# Esquema.net
KiCad netlist of a schematic drawn in EAGLE
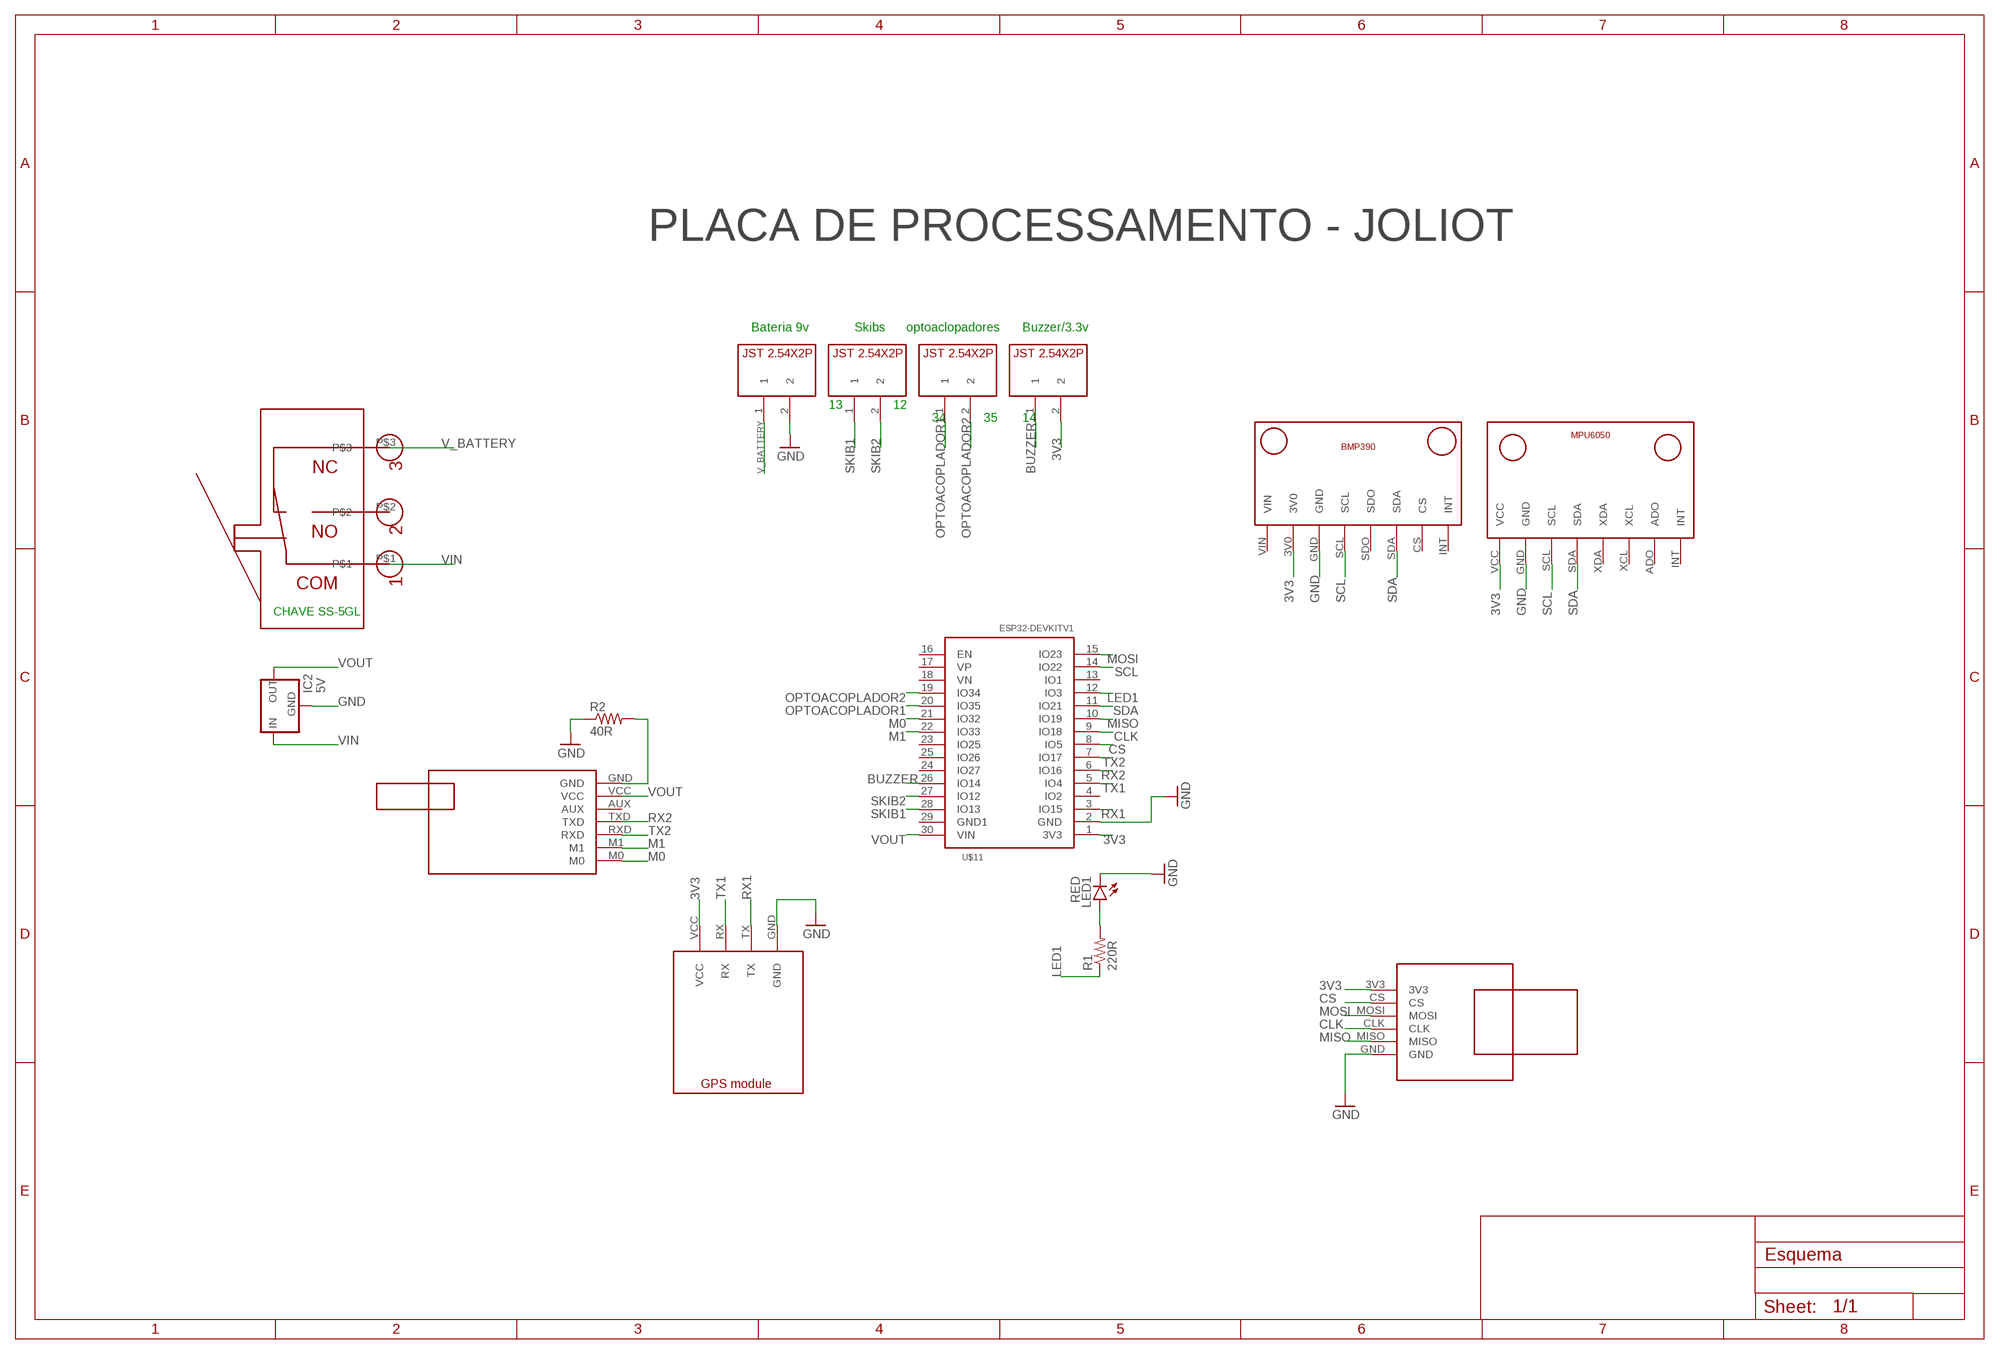
[diagram p0: schematic, sheet 1]

(export (version "E")
  (design (tool "Eeschema 10.0.6"))
  (components
    (comp (ref "IC2")
      (value "5V")
      (footprint "eagle-import:78XXL")
      (libsource (lib "eagle-import") (part "78XXL"))
    )
    (comp (ref "LED1")
      (value "RED")
      (footprint "eagle-import:LED5MM")
      (libsource (lib "eagle-import") (part "LED5MM"))
    )
    (comp (ref "R1")
      (value "220R")
      (footprint "eagle-import:0309_12")
      (libsource (lib "eagle-import") (part "R-US_0309/12"))
    )
    (comp (ref "R2")
      (value "40R")
      (footprint "eagle-import:0309_12")
      (libsource (lib "eagle-import") (part "R-US_0309/12"))
    )
    (comp (ref "U$1")
      (value "BMP390V1")
      (footprint "eagle-import:BMP390_FOOTPRINT")
      (libsource (lib "eagle-import") (part "BMP390V1"))
    )
    (comp (ref "U$2")
      (value "E22-400T30D")
      (footprint "eagle-import:E22-400T30D_FOOTPRINT")
      (libsource (lib "eagle-import") (part "E22-400T30D"))
    )
    (comp (ref "U$3")
      (value "GPS_MODULE")
      (footprint "eagle-import:GPS_MODULE_FOOTPRINT")
      (libsource (lib "eagle-import") (part "GPS_MODULE"))
    )
    (comp (ref "U$4")
      (value "JST2.54X2P")
      (footprint "eagle-import:JST2.54X2P_FOOTPRINT")
      (libsource (lib "eagle-import") (part "JST2.54X2P"))
    )
    (comp (ref "U$5")
      (value "JST2.54X2P")
      (footprint "eagle-import:JST2.54X2P_FOOTPRINT")
      (libsource (lib "eagle-import") (part "JST2.54X2P"))
    )
    (comp (ref "U$6")
      (value "JST2.54X2P")
      (footprint "eagle-import:JST2.54X2P_FOOTPRINT")
      (libsource (lib "eagle-import") (part "JST2.54X2P"))
    )
    (comp (ref "U$7")
      (value "JST2.54X2P")
      (footprint "eagle-import:JST2.54X2P_FOOTPRINT")
      (libsource (lib "eagle-import") (part "JST2.54X2P"))
    )
    (comp (ref "U$8")
      (value "MICROSD_SMALL_READER")
      (footprint "eagle-import:MICROSD_SMALL_READER_FOOTPRINT")
      (libsource (lib "eagle-import") (part "MICROSD_SMALL_READER"))
    )
    (comp (ref "U$9")
      (value "MPU6050V1")
      (footprint "eagle-import:MPU6050_FOOTPRINT")
      (libsource (lib "eagle-import") (part "MPU6050V1"))
    )
    (comp (ref "U$11")
      (value "ESP32DEVKITV1")
      (footprint "eagle-import:ESP32-DEVKITV1")
      (libsource (lib "eagle-import") (part "ESP32DEVKITV1"))
    )
    (comp (ref "U$12")
      (value "CHAVE_SS-5GL")
      (footprint "eagle-import:CHAVESS-5GL")
      (libsource (lib "eagle-import") (part "CHAVE_SS-5GL"))
    )
  )
  (nets
    (net (code "1") (name "/3V3") (class "Default")
      (node (ref "U$1") (pin "3V0") (pinfunction "3V0_3V0") (pintype "bidirectional"))
      (node (ref "U$11") (pin "1") (pinfunction "3V3_1") (pintype "bidirectional"))
      (node (ref "U$3") (pin "VCC") (pinfunction "VCC_VCC") (pintype "bidirectional"))
      (node (ref "U$4") (pin "2") (pinfunction "2_2") (pintype "bidirectional"))
      (node (ref "U$8") (pin "3V3") (pinfunction "3V3_3V3") (pintype "bidirectional"))
      (node (ref "U$9") (pin "VCC") (pinfunction "VCC_VCC") (pintype "bidirectional"))
    )
    (net (code "2") (name "/BUZZER") (class "Default")
      (node (ref "U$11") (pin "26") (pinfunction "IO14_26") (pintype "bidirectional"))
      (node (ref "U$4") (pin "1") (pinfunction "1_1") (pintype "bidirectional"))
    )
    (net (code "3") (name "/CLK") (class "Default")
      (node (ref "U$11") (pin "9") (pinfunction "IO18_9") (pintype "bidirectional"))
      (node (ref "U$8") (pin "CLK") (pinfunction "CLK_CLK") (pintype "bidirectional"))
    )
    (net (code "4") (name "/CS") (class "Default")
      (node (ref "U$11") (pin "8") (pinfunction "IO5_8") (pintype "bidirectional"))
      (node (ref "U$8") (pin "CS") (pinfunction "CS_CS") (pintype "bidirectional"))
    )
    (net (code "5") (name "/LED1") (class "Default")
      (node (ref "R1") (pin "1") (pinfunction "1_1") (pintype "passive"))
      (node (ref "U$11") (pin "12") (pinfunction "IO3_12") (pintype "bidirectional"))
    )
    (net (code "6") (name "/M0") (class "Default")
      (node (ref "U$11") (pin "21") (pinfunction "IO32_21") (pintype "bidirectional"))
      (node (ref "U$2") (pin "M0") (pinfunction "M0_M0") (pintype "bidirectional"))
    )
    (net (code "7") (name "/M1") (class "Default")
      (node (ref "U$11") (pin "22") (pinfunction "IO33_22") (pintype "bidirectional"))
      (node (ref "U$2") (pin "M1") (pinfunction "M1_M1") (pintype "bidirectional"))
    )
    (net (code "8") (name "/MISO") (class "Default")
      (node (ref "U$11") (pin "10") (pinfunction "IO19_10") (pintype "bidirectional"))
      (node (ref "U$8") (pin "MISO") (pinfunction "MISO_MISO") (pintype "bidirectional"))
    )
    (net (code "9") (name "/MOSI") (class "Default")
      (node (ref "U$11") (pin "15") (pinfunction "IO23_15") (pintype "bidirectional"))
      (node (ref "U$8") (pin "MOSI") (pinfunction "MOSI_MOSI") (pintype "bidirectional"))
    )
    (net (code "10") (name "/OPTOACOPLADOR1") (class "Default")
      (node (ref "U$11") (pin "20") (pinfunction "IO35_20") (pintype "bidirectional"))
      (node (ref "U$5") (pin "1") (pinfunction "1_1") (pintype "bidirectional"))
    )
    (net (code "11") (name "/OPTOACOPLADOR2") (class "Default")
      (node (ref "U$11") (pin "19") (pinfunction "IO34_19") (pintype "bidirectional"))
      (node (ref "U$5") (pin "2") (pinfunction "2_2") (pintype "bidirectional"))
    )
    (net (code "12") (name "/RX1") (class "Default")
      (node (ref "U$11") (pin "3") (pinfunction "IO15_3") (pintype "bidirectional"))
      (node (ref "U$3") (pin "TX") (pinfunction "TX_TX") (pintype "bidirectional"))
    )
    (net (code "13") (name "/RX2") (class "Default")
      (node (ref "U$11") (pin "6") (pinfunction "IO16_6") (pintype "bidirectional"))
      (node (ref "U$2") (pin "TXD") (pinfunction "TXD_TXD") (pintype "bidirectional"))
    )
    (net (code "14") (name "/SCL") (class "Default")
      (node (ref "U$1") (pin "SCL") (pinfunction "SCL_SCL") (pintype "bidirectional"))
      (node (ref "U$11") (pin "14") (pinfunction "IO22_14") (pintype "bidirectional"))
      (node (ref "U$9") (pin "SCL") (pinfunction "SCL_SCL") (pintype "bidirectional"))
    )
    (net (code "15") (name "/SDA") (class "Default")
      (node (ref "U$1") (pin "SDA") (pinfunction "SDA_SDA") (pintype "bidirectional"))
      (node (ref "U$11") (pin "11") (pinfunction "IO21_11") (pintype "bidirectional"))
      (node (ref "U$9") (pin "SDA") (pinfunction "SDA_SDA") (pintype "bidirectional"))
    )
    (net (code "16") (name "/SKIB1") (class "Default")
      (node (ref "U$11") (pin "28") (pinfunction "IO13_28") (pintype "bidirectional"))
      (node (ref "U$6") (pin "1") (pinfunction "1_1") (pintype "bidirectional"))
    )
    (net (code "17") (name "/SKIB2") (class "Default")
      (node (ref "U$11") (pin "27") (pinfunction "IO12_27") (pintype "bidirectional"))
      (node (ref "U$6") (pin "2") (pinfunction "2_2") (pintype "bidirectional"))
    )
    (net (code "18") (name "/TX1") (class "Default")
      (node (ref "U$11") (pin "5") (pinfunction "IO4_5") (pintype "bidirectional"))
      (node (ref "U$3") (pin "RX") (pinfunction "RX_RX") (pintype "bidirectional"))
    )
    (net (code "19") (name "/TX2") (class "Default")
      (node (ref "U$11") (pin "7") (pinfunction "IO17_7") (pintype "bidirectional"))
      (node (ref "U$2") (pin "RXD") (pinfunction "RXD_RXD") (pintype "bidirectional"))
    )
    (net (code "20") (name "/VIN") (class "Default")
      (node (ref "IC2") (pin "IN") (pinfunction "IN_IN") (pintype "input"))
      (node (ref "U$12") (pin "P$1") (pinfunction "P$1_P$1") (pintype "bidirectional"))
    )
    (net (code "21") (name "/VOUT") (class "Default")
      (node (ref "IC2") (pin "OUT") (pinfunction "OUT_OUT") (pintype "passive"))
      (node (ref "U$11") (pin "30") (pinfunction "VIN_30") (pintype "bidirectional"))
      (node (ref "U$2") (pin "VCC") (pinfunction "VCC_VCC") (pintype "bidirectional"))
    )
    (net (code "22") (name "/V_BATTERY") (class "Default")
      (node (ref "U$12") (pin "P$3") (pinfunction "P$3_P$3") (pintype "bidirectional"))
      (node (ref "U$7") (pin "1") (pinfunction "1_1") (pintype "bidirectional"))
    )
    (net (code "23") (name "GND") (class "Default")
      (node (ref "IC2") (pin "GND") (pinfunction "GND_GND") (pintype "input"))
      (node (ref "LED1") (pin "K") (pinfunction "C_K") (pintype "passive"))
      (node (ref "R2") (pin "1") (pinfunction "1_1") (pintype "passive"))
      (node (ref "U$1") (pin "GND") (pinfunction "GND_GND") (pintype "bidirectional"))
      (node (ref "U$11") (pin "2") (pinfunction "GND_2") (pintype "bidirectional"))
      (node (ref "U$3") (pin "GND") (pinfunction "GND_GND") (pintype "bidirectional"))
      (node (ref "U$7") (pin "2") (pinfunction "2_2") (pintype "bidirectional"))
      (node (ref "U$8") (pin "GND") (pinfunction "GND_GND") (pintype "bidirectional"))
      (node (ref "U$9") (pin "GND") (pinfunction "GND_GND") (pintype "bidirectional"))
    )
    (net (code "24") (name "Net-(LED1-PadA)") (class "Default")
      (node (ref "LED1") (pin "A") (pinfunction "A_A") (pintype "passive"))
      (node (ref "R1") (pin "2") (pinfunction "2_2") (pintype "passive"))
    )
    (net (code "25") (name "Net-(R2-Pad2)") (class "Default")
      (node (ref "R2") (pin "2") (pinfunction "2_2") (pintype "passive"))
      (node (ref "U$2") (pin "GND") (pinfunction "GND_GND") (pintype "bidirectional"))
    )
    (net (code "26") (name "unconnected-(U$1-PadCS)") (class "Default")
      (node (ref "U$1") (pin "CS") (pinfunction "CS_CS") (pintype "bidirectional"))
    )
    (net (code "27") (name "unconnected-(U$1-PadINT)") (class "Default")
      (node (ref "U$1") (pin "INT") (pinfunction "INT_INT") (pintype "bidirectional"))
    )
    (net (code "28") (name "unconnected-(U$1-PadSDO)") (class "Default")
      (node (ref "U$1") (pin "SDO") (pinfunction "SDO_SDO") (pintype "bidirectional"))
    )
    (net (code "29") (name "unconnected-(U$1-PadVIN)") (class "Default")
      (node (ref "U$1") (pin "VIN") (pinfunction "VIN_VIN") (pintype "bidirectional"))
    )
    (net (code "30") (name "unconnected-(U$2-PadAUX)") (class "Default")
      (node (ref "U$2") (pin "AUX") (pinfunction "AUX_AUX") (pintype "bidirectional"))
    )
    (net (code "31") (name "unconnected-(U$9-PadADO)") (class "Default")
      (node (ref "U$9") (pin "ADO") (pinfunction "ADO_ADO") (pintype "bidirectional"))
    )
    (net (code "32") (name "unconnected-(U$9-PadINT)") (class "Default")
      (node (ref "U$9") (pin "INT") (pinfunction "INT_INT") (pintype "bidirectional"))
    )
    (net (code "33") (name "unconnected-(U$9-PadXCL)") (class "Default")
      (node (ref "U$9") (pin "XCL") (pinfunction "XCL_XCL") (pintype "bidirectional"))
    )
    (net (code "34") (name "unconnected-(U$9-PadXDA)") (class "Default")
      (node (ref "U$9") (pin "XDA") (pinfunction "XDA_XDA") (pintype "bidirectional"))
    )
    (net (code "35") (name "unconnected-(U$11-EN-Pad16)") (class "Default")
      (node (ref "U$11") (pin "16") (pinfunction "EN_16") (pintype "bidirectional"))
    )
    (net (code "36") (name "unconnected-(U$11-GND1-Pad29)") (class "Default")
      (node (ref "U$11") (pin "29") (pinfunction "GND1_29") (pintype "bidirectional"))
    )
    (net (code "37") (name "unconnected-(U$11-IO1-Pad13)") (class "Default")
      (node (ref "U$11") (pin "13") (pinfunction "IO1_13") (pintype "bidirectional"))
    )
    (net (code "38") (name "unconnected-(U$11-IO2-Pad4)") (class "Default")
      (node (ref "U$11") (pin "4") (pinfunction "IO2_4") (pintype "bidirectional"))
    )
    (net (code "39") (name "unconnected-(U$11-IO25-Pad23)") (class "Default")
      (node (ref "U$11") (pin "23") (pinfunction "IO25_23") (pintype "bidirectional"))
    )
    (net (code "40") (name "unconnected-(U$11-IO26-Pad25)") (class "Default")
      (node (ref "U$11") (pin "25") (pinfunction "IO26_25") (pintype "bidirectional"))
    )
    (net (code "41") (name "unconnected-(U$11-IO27-Pad24)") (class "Default")
      (node (ref "U$11") (pin "24") (pinfunction "IO27_24") (pintype "bidirectional"))
    )
    (net (code "42") (name "unconnected-(U$11-VN-Pad18)") (class "Default")
      (node (ref "U$11") (pin "18") (pinfunction "VN_18") (pintype "bidirectional"))
    )
    (net (code "43") (name "unconnected-(U$11-VP-Pad17)") (class "Default")
      (node (ref "U$11") (pin "17") (pinfunction "VP_17") (pintype "bidirectional"))
    )
    (net (code "44") (name "unconnected-(U$12-PadP$2)") (class "Default")
      (node (ref "U$12") (pin "P$2") (pinfunction "P$2_P$2") (pintype "bidirectional"))
    )
  )
)
